# SCH_motor-driver_2025-12-12.net
KiCad netlist of a schematic drawn in EasyEDA
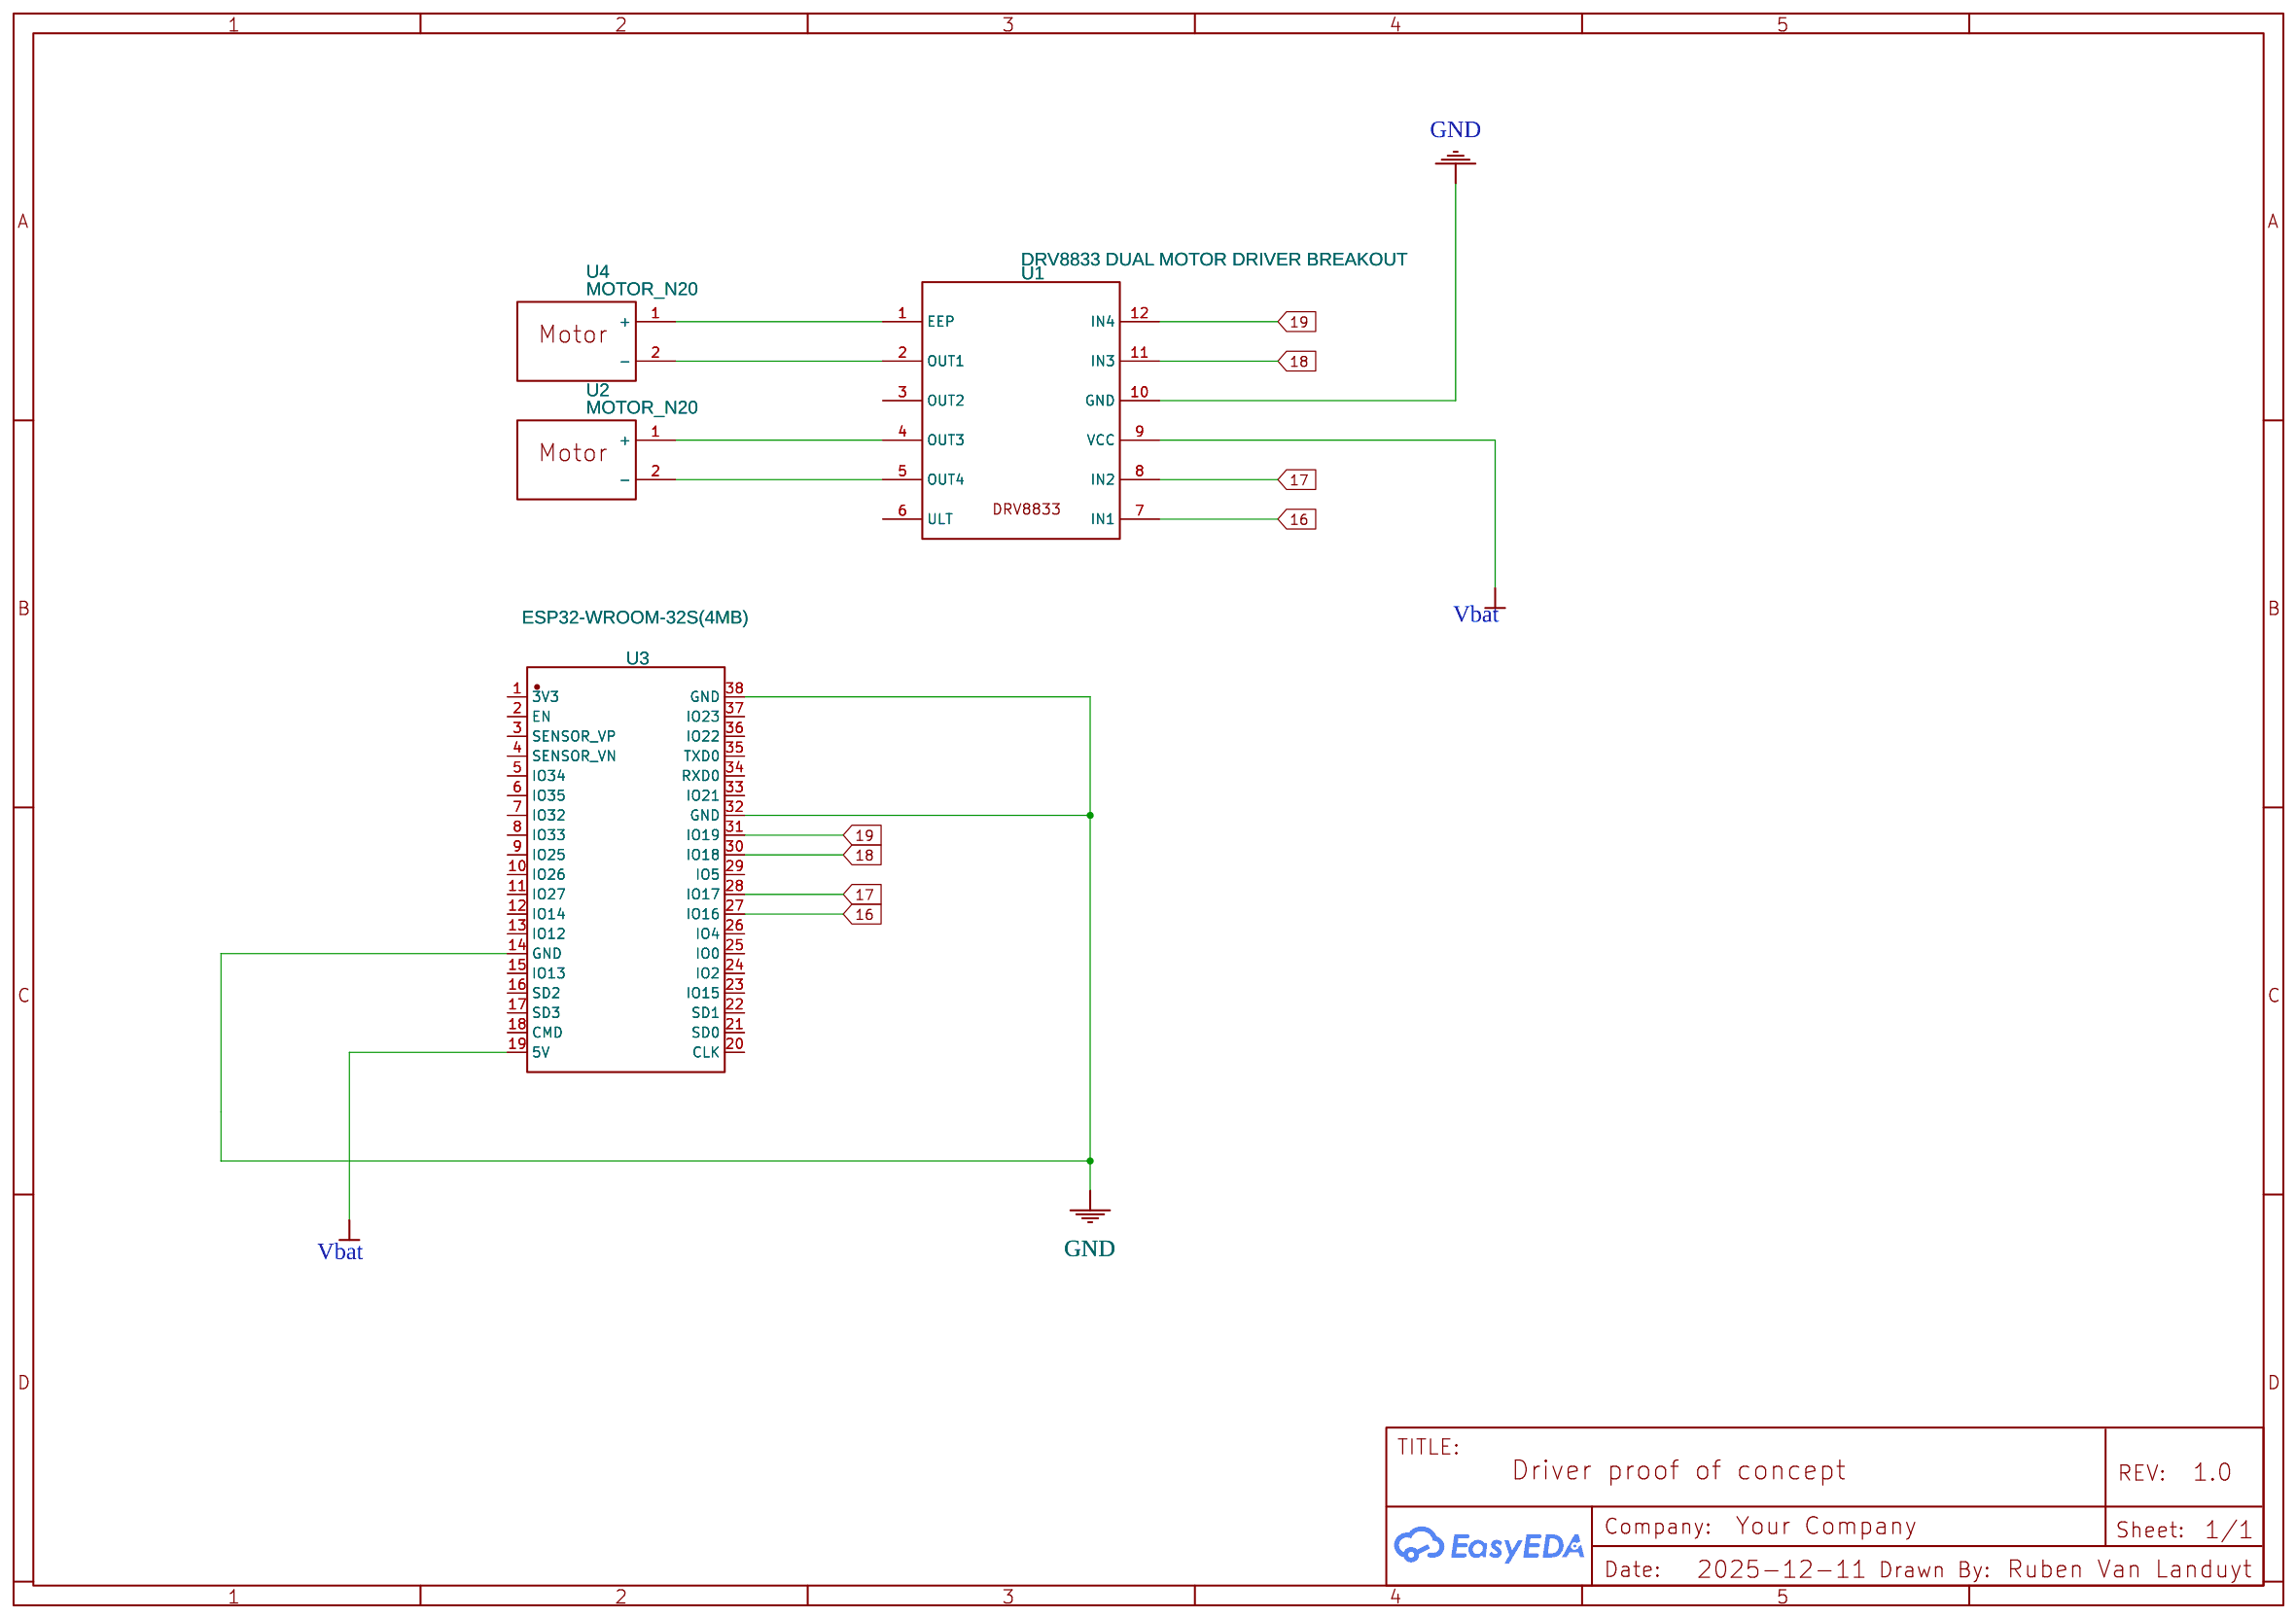
[diagram p0: schematic sheet]

(export (version "E")
  (design (tool "Eeschema 10.0.6"))
  (components
    (comp (ref "U1")
      (value "DRV8833 DUAL MOTOR DRIVER BREAKOUT")
      (libsource (lib "") (part "DRV8833 DUAL MOTOR DRIVER BREAKOUT"))
    )
    (comp (ref "U2") (value "MOTOR_N20") (libsource (lib "") (part "MOTOR_N20")))
    (comp (ref "U3")
      (value "ESP32-WROOM-32S(4MB)")
      (fields (field (name "Manufacturer") "Espressif Systems"))
      (libsource (lib "") (part "ESP32-WROOM-32S(4MB)"))
    )
    (comp (ref "U4") (value "MOTOR_N20") (libsource (lib "") (part "MOTOR_N20")))
  )
  (nets
    (net (code "1") (name "16") (class "Default")
      (node (ref "U1") (pin "7") (pinfunction "IN1_7") (pintype "unspecified"))
      (node (ref "U3") (pin "27") (pinfunction "IO16_27") (pintype "unspecified"))
    )
    (net (code "2") (name "17") (class "Default")
      (node (ref "U1") (pin "8") (pinfunction "IN2_8") (pintype "unspecified"))
      (node (ref "U3") (pin "28") (pinfunction "IO17_28") (pintype "unspecified"))
    )
    (net (code "3") (name "18") (class "Default")
      (node (ref "U1") (pin "11") (pinfunction "IN3_11") (pintype "unspecified"))
      (node (ref "U3") (pin "30") (pinfunction "IO18_30") (pintype "unspecified"))
    )
    (net (code "4") (name "19") (class "Default")
      (node (ref "U1") (pin "12") (pinfunction "IN4_12") (pintype "unspecified"))
      (node (ref "U3") (pin "31") (pinfunction "IO19_31") (pintype "unspecified"))
    )
    (net (code "5") (name "GND") (class "Default")
      (node (ref "U1") (pin "10") (pinfunction "GND_10") (pintype "unspecified"))
      (node (ref "U3") (pin "14") (pinfunction "GND_14") (pintype "unspecified"))
      (node (ref "U3") (pin "32") (pinfunction "GND_32") (pintype "unspecified"))
      (node (ref "U3") (pin "38") (pinfunction "GND_38") (pintype "unspecified"))
    )
    (net (code "6") (name "Net-(U1-EEP)") (class "Default")
      (node (ref "U1") (pin "1") (pinfunction "EEP_1") (pintype "unspecified"))
      (node (ref "U4") (pin "1") (pinfunction "+_1") (pintype "unspecified"))
    )
    (net (code "7") (name "Net-(U1-OUT1)") (class "Default")
      (node (ref "U1") (pin "2") (pinfunction "OUT1_2") (pintype "unspecified"))
      (node (ref "U4") (pin "2") (pinfunction "-_2") (pintype "unspecified"))
    )
    (net (code "8") (name "Net-(U1-OUT3)") (class "Default")
      (node (ref "U1") (pin "4") (pinfunction "OUT3_4") (pintype "unspecified"))
      (node (ref "U2") (pin "1") (pinfunction "+_1") (pintype "unspecified"))
    )
    (net (code "9") (name "Net-(U1-OUT4)") (class "Default")
      (node (ref "U1") (pin "5") (pinfunction "OUT4_5") (pintype "unspecified"))
      (node (ref "U2") (pin "2") (pinfunction "-_2") (pintype "unspecified"))
    )
    (net (code "10") (name "Vbat") (class "Default")
      (node (ref "U1") (pin "9") (pinfunction "VCC_9") (pintype "unspecified"))
      (node (ref "U3") (pin "19") (pinfunction "5V_19") (pintype "unspecified"))
    )
    (net (code "11") (name "unconnected-(U1-OUT2-Pad3)") (class "Default")
      (node (ref "U1") (pin "3") (pinfunction "OUT2_3") (pintype "unspecified"))
    )
    (net (code "12") (name "unconnected-(U1-ULT-Pad6)") (class "Default")
      (node (ref "U1") (pin "6") (pinfunction "ULT_6") (pintype "unspecified"))
    )
    (net (code "13") (name "unconnected-(U3-3V3-Pad1)") (class "Default")
      (node (ref "U3") (pin "1") (pinfunction "3V3_1") (pintype "unspecified"))
    )
    (net (code "14") (name "unconnected-(U3-CLK-Pad20)") (class "Default")
      (node (ref "U3") (pin "20") (pinfunction "CLK_20") (pintype "unspecified"))
    )
    (net (code "15") (name "unconnected-(U3-CMD-Pad18)") (class "Default")
      (node (ref "U3") (pin "18") (pinfunction "CMD_18") (pintype "unspecified"))
    )
    (net (code "16") (name "unconnected-(U3-EN-Pad2)") (class "Default")
      (node (ref "U3") (pin "2") (pinfunction "EN_2") (pintype "unspecified"))
    )
    (net (code "17") (name "unconnected-(U3-IO0-Pad25)") (class "Default")
      (node (ref "U3") (pin "25") (pinfunction "IO0_25") (pintype "unspecified"))
    )
    (net (code "18") (name "unconnected-(U3-IO2-Pad24)") (class "Default")
      (node (ref "U3") (pin "24") (pinfunction "IO2_24") (pintype "unspecified"))
    )
    (net (code "19") (name "unconnected-(U3-IO4-Pad26)") (class "Default")
      (node (ref "U3") (pin "26") (pinfunction "IO4_26") (pintype "unspecified"))
    )
    (net (code "20") (name "unconnected-(U3-IO5-Pad29)") (class "Default")
      (node (ref "U3") (pin "29") (pinfunction "IO5_29") (pintype "unspecified"))
    )
    (net (code "21") (name "unconnected-(U3-IO12-Pad13)") (class "Default")
      (node (ref "U3") (pin "13") (pinfunction "IO12_13") (pintype "unspecified"))
    )
    (net (code "22") (name "unconnected-(U3-IO13-Pad15)") (class "Default")
      (node (ref "U3") (pin "15") (pinfunction "IO13_15") (pintype "unspecified"))
    )
    (net (code "23") (name "unconnected-(U3-IO14-Pad12)") (class "Default")
      (node (ref "U3") (pin "12") (pinfunction "IO14_12") (pintype "unspecified"))
    )
    (net (code "24") (name "unconnected-(U3-IO15-Pad23)") (class "Default")
      (node (ref "U3") (pin "23") (pinfunction "IO15_23") (pintype "unspecified"))
    )
    (net (code "25") (name "unconnected-(U3-IO21-Pad33)") (class "Default")
      (node (ref "U3") (pin "33") (pinfunction "IO21_33") (pintype "unspecified"))
    )
    (net (code "26") (name "unconnected-(U3-IO22-Pad36)") (class "Default")
      (node (ref "U3") (pin "36") (pinfunction "IO22_36") (pintype "unspecified"))
    )
    (net (code "27") (name "unconnected-(U3-IO23-Pad37)") (class "Default")
      (node (ref "U3") (pin "37") (pinfunction "IO23_37") (pintype "unspecified"))
    )
    (net (code "28") (name "unconnected-(U3-IO25-Pad9)") (class "Default")
      (node (ref "U3") (pin "9") (pinfunction "IO25_9") (pintype "unspecified"))
    )
    (net (code "29") (name "unconnected-(U3-IO26-Pad10)") (class "Default")
      (node (ref "U3") (pin "10") (pinfunction "IO26_10") (pintype "unspecified"))
    )
    (net (code "30") (name "unconnected-(U3-IO27-Pad11)") (class "Default")
      (node (ref "U3") (pin "11") (pinfunction "IO27_11") (pintype "unspecified"))
    )
    (net (code "31") (name "unconnected-(U3-IO32-Pad7)") (class "Default")
      (node (ref "U3") (pin "7") (pinfunction "IO32_7") (pintype "unspecified"))
    )
    (net (code "32") (name "unconnected-(U3-IO33-Pad8)") (class "Default")
      (node (ref "U3") (pin "8") (pinfunction "IO33_8") (pintype "unspecified"))
    )
    (net (code "33") (name "unconnected-(U3-IO34-Pad5)") (class "Default")
      (node (ref "U3") (pin "5") (pinfunction "IO34_5") (pintype "unspecified"))
    )
    (net (code "34") (name "unconnected-(U3-IO35-Pad6)") (class "Default")
      (node (ref "U3") (pin "6") (pinfunction "IO35_6") (pintype "unspecified"))
    )
    (net (code "35") (name "unconnected-(U3-RXD0-Pad34)") (class "Default")
      (node (ref "U3") (pin "34") (pinfunction "RXD0_34") (pintype "unspecified"))
    )
    (net (code "36") (name "unconnected-(U3-SD0-Pad21)") (class "Default")
      (node (ref "U3") (pin "21") (pinfunction "SD0_21") (pintype "unspecified"))
    )
    (net (code "37") (name "unconnected-(U3-SD1-Pad22)") (class "Default")
      (node (ref "U3") (pin "22") (pinfunction "SD1_22") (pintype "unspecified"))
    )
    (net (code "38") (name "unconnected-(U3-SD2-Pad16)") (class "Default")
      (node (ref "U3") (pin "16") (pinfunction "SD2_16") (pintype "unspecified"))
    )
    (net (code "39") (name "unconnected-(U3-SD3-Pad17)") (class "Default")
      (node (ref "U3") (pin "17") (pinfunction "SD3_17") (pintype "unspecified"))
    )
    (net (code "40") (name "unconnected-(U3-SENSOR_VN-Pad4)") (class "Default")
      (node (ref "U3") (pin "4") (pinfunction "SENSOR_VN_4") (pintype "unspecified"))
    )
    (net (code "41") (name "unconnected-(U3-SENSOR_VP-Pad3)") (class "Default")
      (node (ref "U3") (pin "3") (pinfunction "SENSOR_VP_3") (pintype "unspecified"))
    )
    (net (code "42") (name "unconnected-(U3-TXD0-Pad35)") (class "Default")
      (node (ref "U3") (pin "35") (pinfunction "TXD0_35") (pintype "unspecified"))
    )
  )
)
